# multimedia.net
KiCad netlist of a schematic drawn in Altium Designer
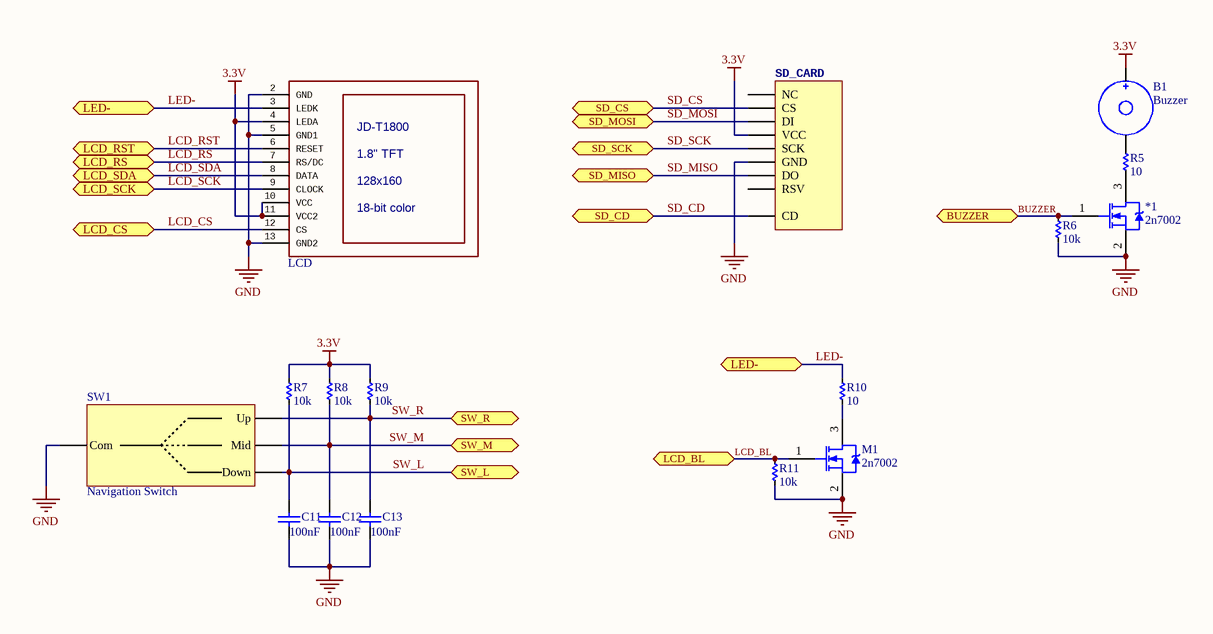
[diagram p0: multimedia.SchDoc]

(export (version "E")
  (design (tool "Eeschema 10.0.6"))
  (components
    (comp (ref "*1") (value "2n7002") (footprint "SOT23_N") (libsource (lib "Mylib") (part "2n7002")))
    (comp (ref "B1") (value "Buzzer") (footprint "Buzzer1") (libsource (lib "Mylib") (part "Buzzer")))
    (comp (ref "C11")
      (value "100nF")
      (footprint "CAPC1608X90N")
      (description "Capacitor (Semiconductor SIM Model)")
      (fields (field (name "Comment") "Cap Semi") (field (name "PUBLISHER") "Altium Limited"))
      (libsource (lib "Mylib") (part "Cap Semi"))
    )
    (comp (ref "C12")
      (value "100nF")
      (footprint "CAPC1608X90N")
      (description "Capacitor (Semiconductor SIM Model)")
      (fields (field (name "Comment") "Cap Semi") (field (name "PUBLISHER") "Altium Limited"))
      (libsource (lib "Mylib") (part "Cap Semi"))
    )
    (comp (ref "C13")
      (value "100nF")
      (footprint "CAPC1608X90N")
      (description "Capacitor (Semiconductor SIM Model)")
      (fields (field (name "Comment") "Cap Semi") (field (name "PUBLISHER") "Altium Limited"))
      (libsource (lib "Mylib") (part "Cap Semi"))
    )
    (comp (ref "LCD")
      (value "LCD_JD-T1800")
      (footprint "JD-T1800")
      (fields
        (field (name "JD-T1800") "JD-T1800")
        (field (name "128X160") "128x160")
        (field (name "18-BITCOLOR") "18-bit color")
        (field (name "1.8\"TFT") "1.8\" TFT")
      )
      (libsource (lib "Mylib") (part "LCD_JD-T1800"))
    )
    (comp (ref "M1") (value "2n7002") (footprint "SOT23_N") (libsource (lib "Mylib") (part "2n7002")))
    (comp (ref "R5")
      (value "10")
      (footprint "RES-SMD-0603")
      (description "Resistor")
      (fields
        (field (name "MANUFACTURER") "Generic Components")
        (field (name "Comment") "Res")
        (field (name "PUBLISHER") "Altium Hobart Technology Centre")
      )
      (libsource (lib "Mylib") (part "Res-SMD"))
    )
    (comp (ref "R6")
      (value "10k")
      (footprint "RES-SMD-0603")
      (description "Resistor")
      (fields
        (field (name "MANUFACTURER") "Generic Components")
        (field (name "Comment") "Res")
        (field (name "PUBLISHER") "Altium Hobart Technology Centre")
      )
      (libsource (lib "Mylib") (part "Res-SMD"))
    )
    (comp (ref "R7")
      (value "10k")
      (footprint "RES-SMD-0603")
      (description "Resistor")
      (fields
        (field (name "MANUFACTURER") "Generic Components")
        (field (name "Comment") "Res")
        (field (name "PUBLISHER") "Altium Hobart Technology Centre")
      )
      (libsource (lib "Mylib") (part "Res-SMD"))
    )
    (comp (ref "R8")
      (value "10k")
      (footprint "RES-SMD-0603")
      (description "Resistor")
      (fields
        (field (name "MANUFACTURER") "Generic Components")
        (field (name "Comment") "Res")
        (field (name "PUBLISHER") "Altium Hobart Technology Centre")
      )
      (libsource (lib "Mylib") (part "Res-SMD"))
    )
    (comp (ref "R9")
      (value "10k")
      (footprint "RES-SMD-0603")
      (description "Resistor")
      (fields
        (field (name "MANUFACTURER") "Generic Components")
        (field (name "Comment") "Res")
        (field (name "PUBLISHER") "Altium Hobart Technology Centre")
      )
      (libsource (lib "Mylib") (part "Res-SMD"))
    )
    (comp (ref "R10")
      (value "10")
      (footprint "RES-SMD-0603")
      (description "Resistor")
      (fields
        (field (name "MANUFACTURER") "Generic Components")
        (field (name "Comment") "Res")
        (field (name "PUBLISHER") "Altium Hobart Technology Centre")
      )
      (libsource (lib "Mylib") (part "Res-SMD"))
    )
    (comp (ref "R11")
      (value "10k")
      (footprint "RES-SMD-0603")
      (description "Resistor")
      (fields
        (field (name "MANUFACTURER") "Generic Components")
        (field (name "Comment") "Res")
        (field (name "PUBLISHER") "Altium Hobart Technology Centre")
      )
      (libsource (lib "Mylib") (part "Res-SMD"))
    )
    (comp (ref "SD_CARD")
      (value "USD-SOCKETUSD")
      (footprint "MicroSD-CARD")
      (libsource (lib "Mylib") (part "USD-SOCKETUSD"))
    )
    (comp (ref "SW1")
      (value "Navigation Switch")
      (footprint "Navigation Switch")
      (libsource (lib "Mylib") (part "Navigation Switch"))
    )
  )
  (nets
    (net (code "1") (name "/BUZZER") (class "Default")
      (node (ref "*1") (pin "1") (pinfunction "G_1") (pintype "passive"))
      (node (ref "R6") (pin "1") (pinfunction "1_1") (pintype "passive"))
    )
    (net (code "2") (name "/LCD_BL") (class "Default")
      (node (ref "M1") (pin "1") (pinfunction "G_1") (pintype "passive"))
      (node (ref "R11") (pin "1") (pinfunction "1_1") (pintype "passive"))
    )
    (net (code "3") (name "/LCD_CS") (class "Default")
      (node (ref "LCD") (pin "12") (pinfunction "CS_12") (pintype "passive"))
    )
    (net (code "4") (name "/LCD_RS") (class "Default")
      (node (ref "LCD") (pin "7") (pinfunction "RS/DC_7") (pintype "passive"))
    )
    (net (code "5") (name "/LCD_RST") (class "Default")
      (node (ref "LCD") (pin "6") (pinfunction "RESET_6") (pintype "passive"))
    )
    (net (code "6") (name "/LCD_SCK") (class "Default")
      (node (ref "LCD") (pin "9") (pinfunction "CLOCK_9") (pintype "passive"))
    )
    (net (code "7") (name "/LCD_SDA") (class "Default")
      (node (ref "LCD") (pin "8") (pinfunction "DATA_8") (pintype "passive"))
    )
    (net (code "8") (name "/LED-") (class "Default")
      (node (ref "LCD") (pin "3") (pinfunction "LEDK_3") (pintype "passive"))
      (node (ref "R10") (pin "1") (pinfunction "1_1") (pintype "passive"))
    )
    (net (code "9") (name "/SD_CD") (class "Default")
      (node (ref "SD_CARD") (pin "9") (pinfunction "CD_9") (pintype "passive"))
    )
    (net (code "10") (name "/SD_CS") (class "Default")
      (node (ref "SD_CARD") (pin "2") (pinfunction "CS_2") (pintype "passive"))
    )
    (net (code "11") (name "/SD_MISO") (class "Default")
      (node (ref "SD_CARD") (pin "7") (pinfunction "DO_7") (pintype "passive"))
    )
    (net (code "12") (name "/SD_MOSI") (class "Default")
      (node (ref "SD_CARD") (pin "3") (pinfunction "DI_3") (pintype "passive"))
    )
    (net (code "13") (name "/SD_SCK") (class "Default")
      (node (ref "SD_CARD") (pin "5") (pinfunction "SCK_5") (pintype "passive"))
    )
    (net (code "14") (name "/SW_L") (class "Default")
      (node (ref "C11") (pin "2") (pinfunction "2_2") (pintype "passive"))
      (node (ref "R7") (pin "2") (pinfunction "2_2") (pintype "passive"))
      (node (ref "SW1") (pin "3") (pinfunction "Down_3") (pintype "passive"))
    )
    (net (code "15") (name "/SW_M") (class "Default")
      (node (ref "C12") (pin "2") (pinfunction "2_2") (pintype "passive"))
      (node (ref "R8") (pin "2") (pinfunction "2_2") (pintype "passive"))
      (node (ref "SW1") (pin "2") (pinfunction "Mid_2") (pintype "passive"))
    )
    (net (code "16") (name "/SW_R") (class "Default")
      (node (ref "C13") (pin "2") (pinfunction "2_2") (pintype "passive"))
      (node (ref "R9") (pin "2") (pinfunction "2_2") (pintype "passive"))
      (node (ref "SW1") (pin "1") (pinfunction "Up_1") (pintype "passive"))
    )
    (net (code "17") (name "3.3V") (class "Default")
      (node (ref "B1") (pin "1") (pinfunction "1_1") (pintype "passive"))
      (node (ref "LCD") (pin "10") (pinfunction "VCC_10") (pintype "power_in"))
      (node (ref "LCD") (pin "11") (pinfunction "VCC2_11") (pintype "power_in"))
      (node (ref "LCD") (pin "4") (pinfunction "LEDA_4") (pintype "passive"))
      (node (ref "R7") (pin "1") (pinfunction "1_1") (pintype "passive"))
      (node (ref "R8") (pin "1") (pinfunction "1_1") (pintype "passive"))
      (node (ref "R9") (pin "1") (pinfunction "1_1") (pintype "passive"))
      (node (ref "SD_CARD") (pin "4") (pinfunction "VCC_4") (pintype "passive"))
    )
    (net (code "18") (name "GND") (class "Default")
      (node (ref "*1") (pin "2") (pinfunction "S_2") (pintype "passive"))
      (node (ref "C11") (pin "1") (pinfunction "1_1") (pintype "passive"))
      (node (ref "C12") (pin "1") (pinfunction "1_1") (pintype "passive"))
      (node (ref "C13") (pin "1") (pinfunction "1_1") (pintype "passive"))
      (node (ref "LCD") (pin "13") (pinfunction "GND2_13") (pintype "power_in"))
      (node (ref "LCD") (pin "2") (pinfunction "GND_2") (pintype "power_in"))
      (node (ref "LCD") (pin "5") (pinfunction "GND1_5") (pintype "power_in"))
      (node (ref "M1") (pin "2") (pinfunction "S_2") (pintype "passive"))
      (node (ref "R11") (pin "2") (pinfunction "2_2") (pintype "passive"))
      (node (ref "R6") (pin "2") (pinfunction "2_2") (pintype "passive"))
      (node (ref "SD_CARD") (pin "6") (pinfunction "GND_6") (pintype "passive"))
      (node (ref "SW1") (pin "5") (pinfunction "Com_5") (pintype "passive"))
    )
    (net (code "19") (name "Net-(*1-D)") (class "Default")
      (node (ref "*1") (pin "3") (pinfunction "D_3") (pintype "passive"))
      (node (ref "R5") (pin "2") (pinfunction "2_2") (pintype "passive"))
    )
    (net (code "20") (name "Net-(B1-Pad2)") (class "Default")
      (node (ref "B1") (pin "2") (pinfunction "2_2") (pintype "passive"))
      (node (ref "R5") (pin "1") (pinfunction "1_1") (pintype "passive"))
    )
    (net (code "21") (name "Net-(M1-D)") (class "Default")
      (node (ref "M1") (pin "3") (pinfunction "D_3") (pintype "passive"))
      (node (ref "R10") (pin "2") (pinfunction "2_2") (pintype "passive"))
    )
    (net (code "22") (name "unconnected-(SD_CARD-NC-Pad1)") (class "Default")
      (node (ref "SD_CARD") (pin "1") (pinfunction "NC_1") (pintype "passive"))
    )
    (net (code "23") (name "unconnected-(SD_CARD-RSV-Pad8)") (class "Default")
      (node (ref "SD_CARD") (pin "8") (pinfunction "RSV_8") (pintype "passive"))
    )
  )
)
